# OpenBook.net
KiCad netlist of a schematic drawn in EAGLE
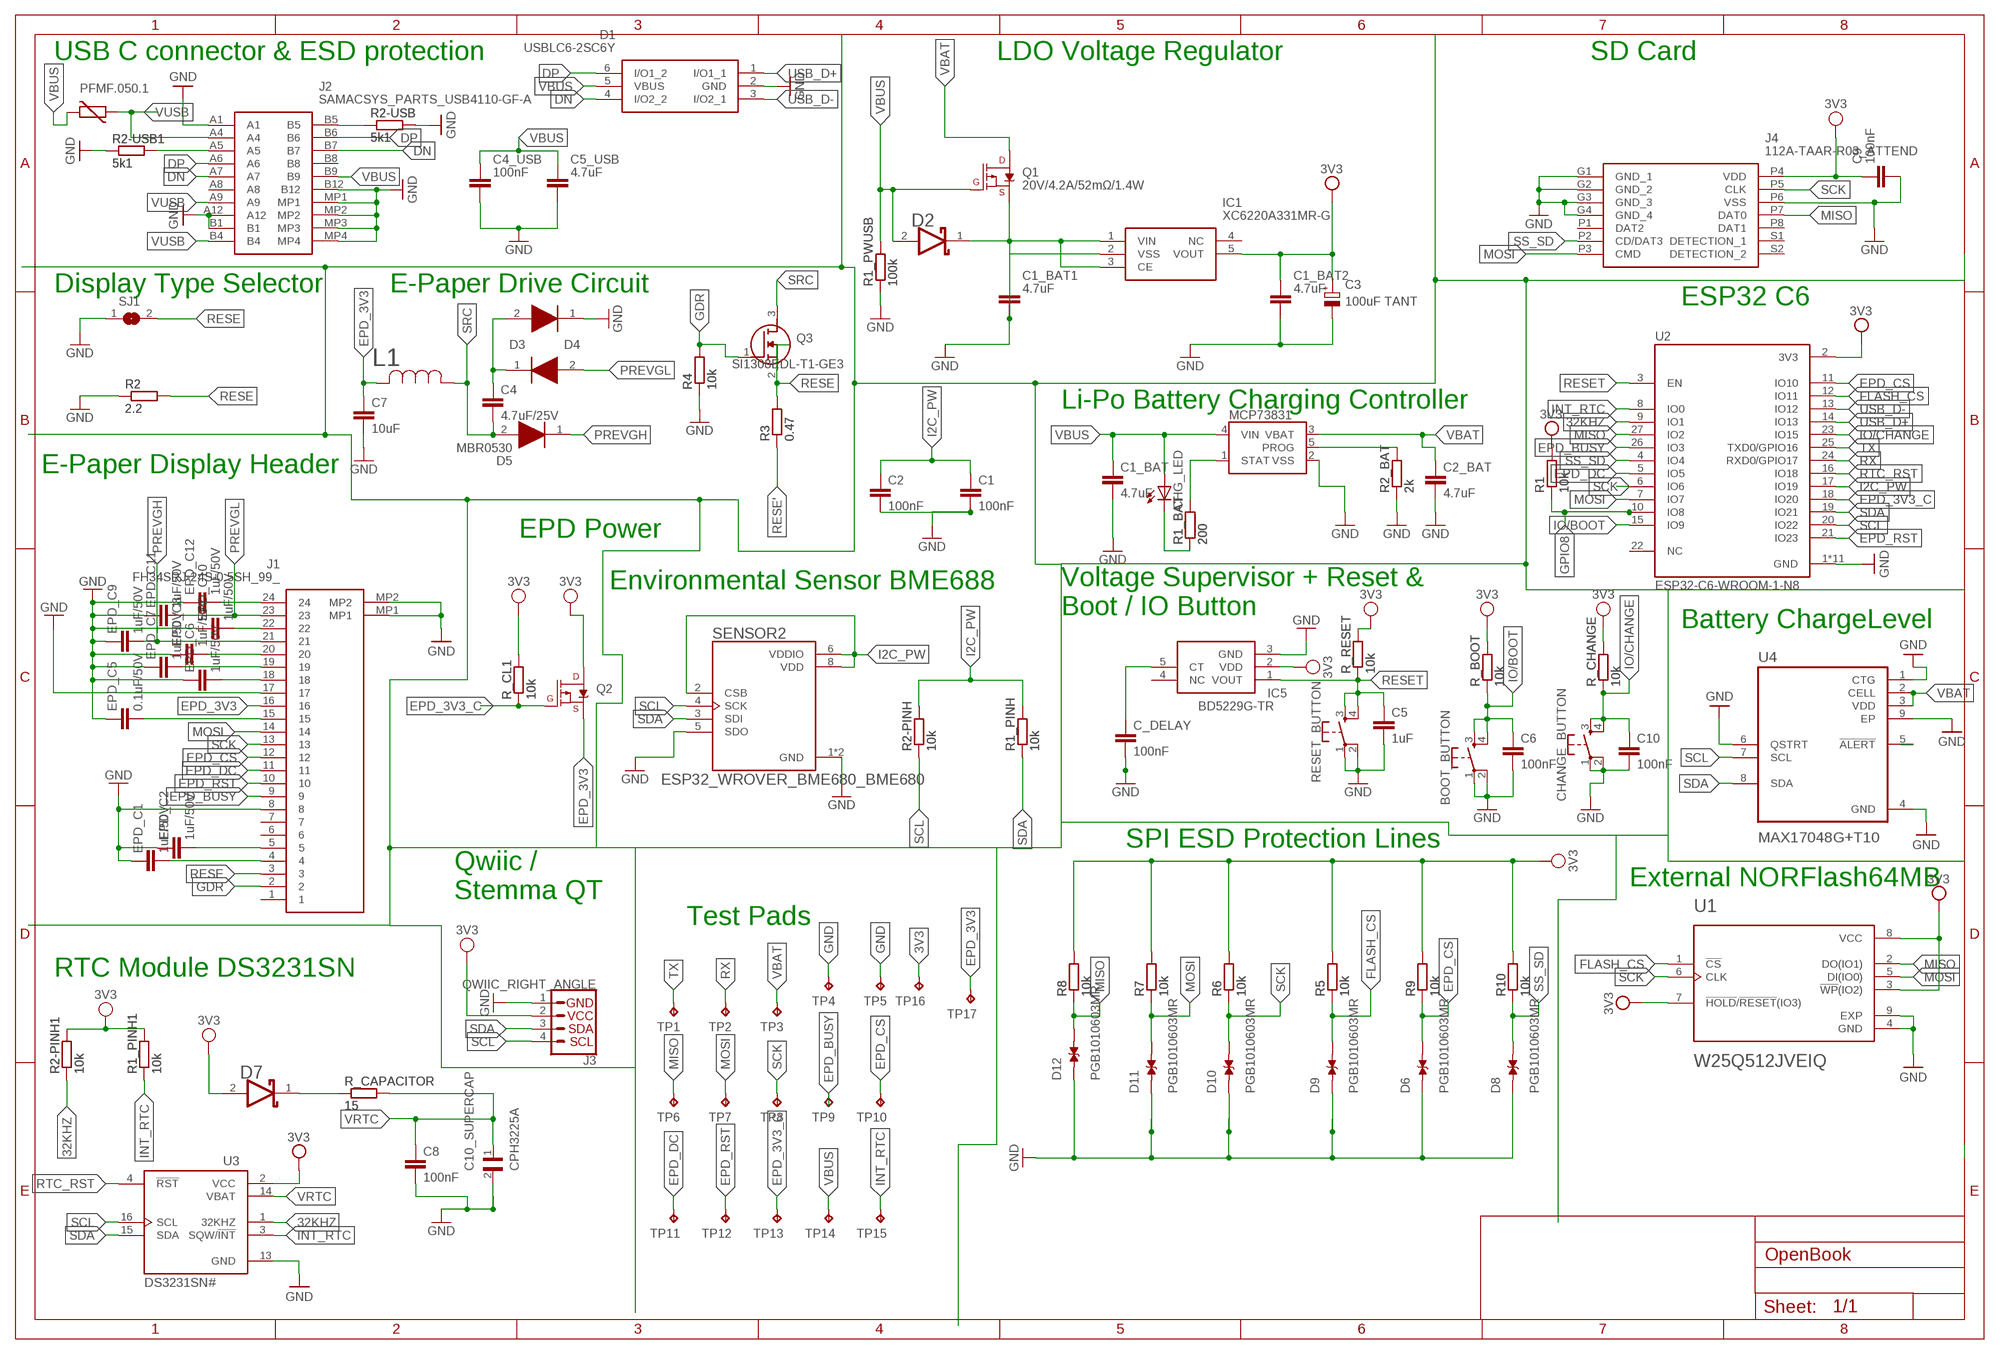
[diagram p0: schematic, sheet 1]

(export (version "E")
  (design (tool "Eeschema 10.0.6"))
  (components
    (comp (ref "BOOT_BUTTON")
      (value "BUTTON_CUSYOMV1")
      (footprint "eagle-import:MYBUTTON")
      (libsource (lib "eagle-import") (part "BUTTON_CUSYOMV1"))
    )
    (comp (ref "C1")
      (value "100nF")
      (footprint "eagle-import:ESP32_WROVER_EAGLE-LTSPICE_C0402")
      (libsource (lib "eagle-import") (part "ESP32_WROVER_EAGLE-LTSPICE_CC0402"))
    )
    (comp (ref "C1_BAT")
      (value "4.7uF")
      (footprint "eagle-import:ESP32_WROVER_EAGLE-LTSPICE_C0402")
      (libsource (lib "eagle-import") (part "ESP32_WROVER_EAGLE-LTSPICE_CC0402"))
    )
    (comp (ref "C1_BAT1")
      (value "4.7uF")
      (footprint "eagle-import:CAPC1005X60")
      (libsource (lib "eagle-import") (part "CCHIP-0402(1005-METRIC)_"))
    )
    (comp (ref "C1_BAT2")
      (value "4.7uF")
      (footprint "eagle-import:CAPM3216X180")
      (libsource (lib "eagle-import") (part "CTANTALUM-1206(3216-METRIC)_"))
    )
    (comp (ref "C2")
      (value "100nF")
      (footprint "eagle-import:ESP32_WROVER_EAGLE-LTSPICE_C0402")
      (libsource (lib "eagle-import") (part "ESP32_WROVER_EAGLE-LTSPICE_CC0402"))
    )
    (comp (ref "C2_BAT")
      (value "4.7uF")
      (footprint "eagle-import:ESP32_WROVER_EAGLE-LTSPICE_C0402")
      (libsource (lib "eagle-import") (part "ESP32_WROVER_EAGLE-LTSPICE_CC0402"))
    )
    (comp (ref "C3")
      (value "100uF TANT")
      (footprint "eagle-import:CAPMP3216X180N")
      (libsource (lib "eagle-import") (part "C-POLTANTALUM-1206(3216-METRIC)_"))
    )
    (comp (ref "C4")
      (value "4.7uF/25V")
      (footprint "eagle-import:EAGLE-LTSPICE_C0402")
      (libsource (lib "eagle-import") (part "EAGLE-LTSPICE_CC0402"))
    )
    (comp (ref "C4_USB")
      (value "100nF")
      (footprint "eagle-import:CAPC1005X60")
      (libsource (lib "eagle-import") (part "CCHIP-0402(1005-METRIC)_"))
    )
    (comp (ref "C5")
      (value "1uF")
      (footprint "eagle-import:ESP32_WROVER_EAGLE-LTSPICE_C0402")
      (libsource (lib "eagle-import") (part "ESP32_WROVER_EAGLE-LTSPICE_CC0402"))
    )
    (comp (ref "C5_USB")
      (value "4.7uF")
      (footprint "eagle-import:CAPC1005X60")
      (libsource (lib "eagle-import") (part "CCHIP-0402(1005-METRIC)_"))
    )
    (comp (ref "C6")
      (value "100nF")
      (footprint "eagle-import:ESP32_WROVER_EAGLE-LTSPICE_C0402")
      (libsource (lib "eagle-import") (part "ESP32_WROVER_EAGLE-LTSPICE_CC0402"))
    )
    (comp (ref "C7")
      (value "10uF")
      (footprint "eagle-import:EAGLE-LTSPICE_C0402")
      (libsource (lib "eagle-import") (part "EAGLE-LTSPICE_CC0402"))
    )
    (comp (ref "C8")
      (value "100nF")
      (footprint "eagle-import:EAGLE-LTSPICE_C0402")
      (libsource (lib "eagle-import") (part "EAGLE-LTSPICE_CC0402"))
    )
    (comp (ref "C9")
      (value "100nF")
      (footprint "eagle-import:CAPC1005X60")
      (libsource (lib "eagle-import") (part "CCHIP-0402(1005-METRIC)_"))
    )
    (comp (ref "C10")
      (value "100nF")
      (footprint "eagle-import:ESP32_WROVER_EAGLE-LTSPICE_C0402")
      (libsource (lib "eagle-import") (part "ESP32_WROVER_EAGLE-LTSPICE_CC0402"))
    )
    (comp (ref "C10_SUPERCAP")
      (value "CPH3225A")
      (footprint "eagle-import:CAPCP3225X100N")
      (fields (field (name "MF") "Seiko Instruments"))
      (libsource (lib "eagle-import") (part "CPH3225A"))
    )
    (comp (ref "CHANGE_BUTTON")
      (value "BUTTON_CUSYOMV1")
      (footprint "eagle-import:MYBUTTON")
      (libsource (lib "eagle-import") (part "BUTTON_CUSYOMV1"))
    )
    (comp (ref "CHG_LED")
      (value "ADAFRUIT_LEDCHIP-LED0603")
      (footprint "eagle-import:ADAFRUIT_CHIP-LED0603")
      (libsource (lib "eagle-import") (part "ADAFRUIT_LEDCHIP-LED0603"))
    )
    (comp (ref "C_DELAY")
      (value "100nF")
      (footprint "eagle-import:ESP32_WROVER_EAGLE-LTSPICE_C0402")
      (libsource (lib "eagle-import") (part "ESP32_WROVER_EAGLE-LTSPICE_CC0402"))
    )
    (comp (ref "D1")
      (value "USBLC6-2SC6Y")
      (footprint "eagle-import:SOT95P280X145-6N")
      (fields (field (name "MF") "STMicroelectronics"))
      (libsource (lib "eagle-import") (part "USBLC6-2SC6Y"))
    )
    (comp (ref "D2")
      (value "ESP32_WROVER_AVX---SD0805S020S1R0_AVX_SD0805S020S1R0_0_0AVX_SD0805S020S1R0_0_0")
      (footprint "eagle-import:ESP32_WROVER_AVX---SD0805S020S1R0_AVX_SD0805S020S1R0_0")
      (fields
        (field (name "DIGIKEY_PART_NUMBER") "478-7800-1-ND")
        (field (name "MF") "AVX")
        (field (name "MOUSER_PART_NUMBER") "581-SD0805S020S1R0")
      )
      (libsource (lib "eagle-import") (part "ESP32_WROVER_AVX---SD0805S020S1R0_AVX_SD0805S020S1R0_0_0AVX_SD0805S020S1R0_0_0"))
    )
    (comp (ref "D3")
      (value "MBR0530")
      (footprint "eagle-import:SOD3716X135N")
      (fields (field (name "MF") "ON Semiconductor"))
      (libsource (lib "eagle-import") (part "MBR0530"))
    )
    (comp (ref "D4")
      (value "MBR0530")
      (footprint "eagle-import:SOD3716X135N")
      (fields (field (name "MF") "ON Semiconductor"))
      (libsource (lib "eagle-import") (part "MBR0530"))
    )
    (comp (ref "D5")
      (value "MBR0530")
      (footprint "eagle-import:SOD3716X135N")
      (fields (field (name "MF") "ON Semiconductor"))
      (libsource (lib "eagle-import") (part "MBR0530"))
    )
    (comp (ref "D6")
      (value "PGB1010603MR")
      (footprint "eagle-import:DIOC1608X36N")
      (fields (field (name "MF") "Littelfuse Inc."))
      (libsource (lib "eagle-import") (part "PGB1010603MR"))
    )
    (comp (ref "D7")
      (value "ESP32_WROVER_AVX---SD0805S020S1R0_AVX_SD0805S020S1R0_0_0AVX_SD0805S020S1R0_0_0")
      (footprint "eagle-import:ESP32_WROVER_AVX---SD0805S020S1R0_AVX_SD0805S020S1R0_0")
      (fields
        (field (name "DIGIKEY_PART_NUMBER") "478-7800-1-ND")
        (field (name "MF") "AVX")
        (field (name "MOUSER_PART_NUMBER") "581-SD0805S020S1R0")
      )
      (libsource (lib "eagle-import") (part "ESP32_WROVER_AVX---SD0805S020S1R0_AVX_SD0805S020S1R0_0_0AVX_SD0805S020S1R0_0_0"))
    )
    (comp (ref "D8")
      (value "PGB1010603MR")
      (footprint "eagle-import:DIOC1608X36N")
      (fields (field (name "MF") "Littelfuse Inc."))
      (libsource (lib "eagle-import") (part "PGB1010603MR"))
    )
    (comp (ref "D9")
      (value "PGB1010603MR")
      (footprint "eagle-import:DIOC1608X36N")
      (fields (field (name "MF") "Littelfuse Inc."))
      (libsource (lib "eagle-import") (part "PGB1010603MR"))
    )
    (comp (ref "D10")
      (value "PGB1010603MR")
      (footprint "eagle-import:DIOC1608X36N")
      (fields (field (name "MF") "Littelfuse Inc."))
      (libsource (lib "eagle-import") (part "PGB1010603MR"))
    )
    (comp (ref "D11")
      (value "PGB1010603MR")
      (footprint "eagle-import:DIOC1608X36N")
      (fields (field (name "MF") "Littelfuse Inc."))
      (libsource (lib "eagle-import") (part "PGB1010603MR"))
    )
    (comp (ref "D12")
      (value "PGB1010603MR")
      (footprint "eagle-import:DIOC1608X36N")
      (fields (field (name "MF") "Littelfuse Inc."))
      (libsource (lib "eagle-import") (part "PGB1010603MR"))
    )
    (comp (ref "EPD_C1")
      (value "1uF/50V")
      (footprint "eagle-import:ESP32_WROVER_EAGLE-LTSPICE_C0402")
      (libsource (lib "eagle-import") (part "ESP32_WROVER_EAGLE-LTSPICE_CC0402"))
    )
    (comp (ref "EPD_C2")
      (value "1uF/50V")
      (footprint "eagle-import:ESP32_WROVER_EAGLE-LTSPICE_C0402")
      (libsource (lib "eagle-import") (part "ESP32_WROVER_EAGLE-LTSPICE_CC0402"))
    )
    (comp (ref "EPD_C5")
      (value "0.1uF/50V")
      (footprint "eagle-import:ESP32_WROVER_EAGLE-LTSPICE_C0402")
      (libsource (lib "eagle-import") (part "ESP32_WROVER_EAGLE-LTSPICE_CC0402"))
    )
    (comp (ref "EPD_C6")
      (value "1uF/50V")
      (footprint "eagle-import:ESP32_WROVER_EAGLE-LTSPICE_C0402")
      (libsource (lib "eagle-import") (part "ESP32_WROVER_EAGLE-LTSPICE_CC0402"))
    )
    (comp (ref "EPD_C7")
      (value "1uF/50V")
      (footprint "eagle-import:ESP32_WROVER_EAGLE-LTSPICE_C0402")
      (libsource (lib "eagle-import") (part "ESP32_WROVER_EAGLE-LTSPICE_CC0402"))
    )
    (comp (ref "EPD_C8")
      (value "1uF/50V")
      (footprint "eagle-import:ESP32_WROVER_EAGLE-LTSPICE_C0402")
      (libsource (lib "eagle-import") (part "ESP32_WROVER_EAGLE-LTSPICE_CC0402"))
    )
    (comp (ref "EPD_C9")
      (value "1uF/50V")
      (footprint "eagle-import:ESP32_WROVER_EAGLE-LTSPICE_C0402")
      (libsource (lib "eagle-import") (part "ESP32_WROVER_EAGLE-LTSPICE_CC0402"))
    )
    (comp (ref "EPD_C10")
      (value "1uF/50V")
      (footprint "eagle-import:ESP32_WROVER_EAGLE-LTSPICE_C0402")
      (libsource (lib "eagle-import") (part "ESP32_WROVER_EAGLE-LTSPICE_CC0402"))
    )
    (comp (ref "EPD_C11")
      (value "1uF/50V")
      (footprint "eagle-import:ESP32_WROVER_EAGLE-LTSPICE_C0402")
      (libsource (lib "eagle-import") (part "ESP32_WROVER_EAGLE-LTSPICE_CC0402"))
    )
    (comp (ref "EPD_C12")
      (value "1uF/50V")
      (footprint "eagle-import:ESP32_WROVER_EAGLE-LTSPICE_C0402")
      (libsource (lib "eagle-import") (part "ESP32_WROVER_EAGLE-LTSPICE_CC0402"))
    )
    (comp (ref "IC1")
      (value "XC6220A331MR-G")
      (footprint "eagle-import:SOT95P280X120-5N")
      (fields (field (name "MOUSER_PART_NUMBER") "865-XC6220A331MR-G"))
      (libsource (lib "eagle-import") (part "XC6220A331MR-G"))
    )
    (comp (ref "IC5")
      (value "BD5229G-TR")
      (footprint "eagle-import:SOT95P280X125-5N")
      (fields (field (name "MOUSER_PART_NUMBER") "755-BD5229G-TR"))
      (libsource (lib "eagle-import") (part "BD5229G-TR"))
    )
    (comp (ref "J1")
      (value "FH34SRJ-24S-0.5SH_99_")
      (footprint "eagle-import:FH34SRJ24S05SH99")
      (fields
        (field (name "MANUFACTURER_PART_NUMBER") "FH34SRJ-24S-0.5SH(99)")
        (field (name "MOUSER_PART_NUMBER") "798-FH34SRJ24S05SH99")
      )
      (libsource (lib "eagle-import") (part "FH34SRJ-24S-0.5SH_99_"))
    )
    (comp (ref "J2")
      (value "SAMACSYS_PARTS_USB4110-GF-A")
      (footprint "eagle-import:SAMACSYS_PARTS_USB4110GFA")
      (fields
        (field (name "MANUFACTURER_PART_NUMBER") "USB4110-GF-A")
        (field (name "MOUSER_PART_NUMBER") "640-USB4110-GF-A")
      )
      (libsource (lib "eagle-import") (part "SAMACSYS_PARTS_USB4110-GF-A"))
    )
    (comp (ref "J3")
      (value "QWIIC_RIGHT_ANGLE")
      (footprint "eagle-import:JST04_1MM_RA")
      (libsource (lib "eagle-import") (part "QWIIC_CONNECTORJS-1MM"))
    )
    (comp (ref "J4")
      (value "112A-TAAR-R03_ATTEND")
      (footprint "eagle-import:112ATAARR03ATTEND")
      (fields (field (name "MANUFACTURER_PART_NUMBER") "112A-TAAR-R03 ATTEND"))
      (libsource (lib "eagle-import") (part "112A-TAAR-R03_ATTEND"))
    )
    (comp (ref "L1")
      (value "68uH")
      (footprint "eagle-import:IND_4828-WE-TPC_WRE")
      (fields
        (field (name "MANUFACTURER_PART_NUMBER") "744043680")
        (field (name "COPYRIGHT") "Copyright (C) 2024 Ultra Librarian. All rights reserved.")
      )
      (libsource (lib "eagle-import") (part "744043680IND_4828-WE-TPC_WRE"))
    )
    (comp (ref "MCP73831")
      (value "ESP32_WROVER_SPARKFUN-IC-POWER_MCP73831")
      (footprint "eagle-import:ESP32_WROVER_SPARKFUN-IC-POWER_SOT23-5")
      (libsource (lib "eagle-import") (part "ESP32_WROVER_SPARKFUN-IC-POWER_MCP73831"))
    )
    (comp (ref "PFMF.050.1")
      (value "ESP32C6_VARISTORCN1812")
      (footprint "eagle-import:ESP32C6_VARISTOR_CT_CN1812")
      (libsource (lib "eagle-import") (part "ESP32C6_VARISTORCN1812"))
    )
    (comp (ref "Q1")
      (value "20V/4.2A/52mΩ/1.4W")
      (footprint "eagle-import:ESP32_WROVER_SPARKFUN-DISCRETESEMI_SOT23-3")
      (libsource (lib "eagle-import") (part "ESP32_WROVER_SPARKFUN-DISCRETESEMI_MOSFET_PCH-DMG2305UX-7"))
    )
    (comp (ref "Q2")
      (value "20V/4.2A/52mΩ/1.4W")
      (footprint "eagle-import:ESP32_WROVER_SPARKFUN-DISCRETESEMI_SOT23-3")
      (libsource (lib "eagle-import") (part "ESP32_WROVER_SPARKFUN-DISCRETESEMI_MOSFET_PCH-DMG2305UX-7"))
    )
    (comp (ref "Q3")
      (value "SI1308EDL-T1-GE3")
      (footprint "eagle-import:SOT65P210X110-3N")
      (fields
        (field (name "MANUFACTURER_PART_NUMBER") "Si1308EDL-T1-GE3")
        (field (name "MOUSER_PART_NUMBER") "78-SI1308EDL-T1-GE3")
      )
      (libsource (lib "eagle-import") (part "SI1308EDL-T1-GE3"))
    )
    (comp (ref "R1")
      (value "10k")
      (footprint "eagle-import:ESP32_WROVER_EAGLE-LTSPICE_R0402")
      (libsource (lib "eagle-import") (part "ESP32_WROVER_EAGLE-LTSPICE_RR0402"))
    )
    (comp (ref "R1_BAT")
      (value "200")
      (footprint "eagle-import:ESP32_WROVER_EAGLE-LTSPICE_R0402")
      (libsource (lib "eagle-import") (part "ESP32_WROVER_EAGLE-LTSPICE_RR0402"))
    )
    (comp (ref "R1_PINH")
      (value "10k")
      (footprint "eagle-import:ESP32_WROVER_EAGLE-LTSPICE_R0402")
      (libsource (lib "eagle-import") (part "ESP32_WROVER_EAGLE-LTSPICE_RR0402"))
    )
    (comp (ref "R1_PINH1")
      (value "10k")
      (footprint "eagle-import:ESP32_WROVER_EAGLE-LTSPICE_R0402")
      (libsource (lib "eagle-import") (part "ESP32_WROVER_EAGLE-LTSPICE_RR0402"))
    )
    (comp (ref "R1_PWUSB")
      (value "100k")
      (footprint "eagle-import:ESP32_WROVER_EAGLE-LTSPICE_R0402")
      (libsource (lib "eagle-import") (part "ESP32_WROVER_EAGLE-LTSPICE_RR0402"))
    )
    (comp (ref "R2")
      (value "2.2")
      (footprint "eagle-import:ESP32_WROVER_EAGLE-LTSPICE_R0402")
      (libsource (lib "eagle-import") (part "ESP32_WROVER_EAGLE-LTSPICE_RR0402"))
    )
    (comp (ref "R2-PINH")
      (value "10k")
      (footprint "eagle-import:ESP32_WROVER_EAGLE-LTSPICE_R0402")
      (libsource (lib "eagle-import") (part "ESP32_WROVER_EAGLE-LTSPICE_RR0402"))
    )
    (comp (ref "R2-PINH1")
      (value "10k")
      (footprint "eagle-import:ESP32_WROVER_EAGLE-LTSPICE_R0402")
      (libsource (lib "eagle-import") (part "ESP32_WROVER_EAGLE-LTSPICE_RR0402"))
    )
    (comp (ref "R2-USB")
      (value "5k1")
      (footprint "eagle-import:ESP32_WROVER_EAGLE-LTSPICE_R0402")
      (libsource (lib "eagle-import") (part "ESP32_WROVER_EAGLE-LTSPICE_RR0402"))
    )
    (comp (ref "R2-USB1")
      (value "5k1")
      (footprint "eagle-import:ESP32_WROVER_EAGLE-LTSPICE_R0402")
      (libsource (lib "eagle-import") (part "ESP32_WROVER_EAGLE-LTSPICE_RR0402"))
    )
    (comp (ref "R2_BAT")
      (value "2k")
      (footprint "eagle-import:ESP32_WROVER_EAGLE-LTSPICE_R0402")
      (libsource (lib "eagle-import") (part "ESP32_WROVER_EAGLE-LTSPICE_RR0402"))
    )
    (comp (ref "R3")
      (value "0.47")
      (footprint "eagle-import:ESP32_WROVER_EAGLE-LTSPICE_R0402")
      (libsource (lib "eagle-import") (part "ESP32_WROVER_EAGLE-LTSPICE_RR0402"))
    )
    (comp (ref "R4")
      (value "10k")
      (footprint "eagle-import:ESP32_WROVER_EAGLE-LTSPICE_R0402")
      (libsource (lib "eagle-import") (part "ESP32_WROVER_EAGLE-LTSPICE_RR0402"))
    )
    (comp (ref "R5")
      (value "10k")
      (footprint "eagle-import:ESP32_WROVER_EAGLE-LTSPICE_R0402")
      (libsource (lib "eagle-import") (part "ESP32_WROVER_EAGLE-LTSPICE_RR0402"))
    )
    (comp (ref "R6")
      (value "10k")
      (footprint "eagle-import:ESP32_WROVER_EAGLE-LTSPICE_R0402")
      (libsource (lib "eagle-import") (part "ESP32_WROVER_EAGLE-LTSPICE_RR0402"))
    )
    (comp (ref "R7")
      (value "10k")
      (footprint "eagle-import:ESP32_WROVER_EAGLE-LTSPICE_R0402")
      (libsource (lib "eagle-import") (part "ESP32_WROVER_EAGLE-LTSPICE_RR0402"))
    )
    (comp (ref "R8")
      (value "10k")
      (footprint "eagle-import:ESP32_WROVER_EAGLE-LTSPICE_R0402")
      (libsource (lib "eagle-import") (part "ESP32_WROVER_EAGLE-LTSPICE_RR0402"))
    )
    (comp (ref "R9")
      (value "10k")
      (footprint "eagle-import:ESP32_WROVER_EAGLE-LTSPICE_R0402")
      (libsource (lib "eagle-import") (part "ESP32_WROVER_EAGLE-LTSPICE_RR0402"))
    )
    (comp (ref "R10")
      (value "10k")
      (footprint "eagle-import:ESP32_WROVER_EAGLE-LTSPICE_R0402")
      (libsource (lib "eagle-import") (part "ESP32_WROVER_EAGLE-LTSPICE_RR0402"))
    )
    (comp (ref "RESET_BUTTON")
      (value "BUTTON_CUSYOMV1")
      (footprint "eagle-import:MYBUTTON")
      (libsource (lib "eagle-import") (part "BUTTON_CUSYOMV1"))
    )
    (comp (ref "R_BOOT")
      (value "10k")
      (footprint "eagle-import:ESP32_WROVER_EAGLE-LTSPICE_R0402")
      (libsource (lib "eagle-import") (part "ESP32_WROVER_EAGLE-LTSPICE_RR0402"))
    )
    (comp (ref "R_CAPACITOR")
      (value "15")
      (footprint "eagle-import:ESP32_WROVER_EAGLE-LTSPICE_R0402")
      (libsource (lib "eagle-import") (part "ESP32_WROVER_EAGLE-LTSPICE_RR0402"))
    )
    (comp (ref "R_CHANGE")
      (value "10k")
      (footprint "eagle-import:ESP32_WROVER_EAGLE-LTSPICE_R0402")
      (libsource (lib "eagle-import") (part "ESP32_WROVER_EAGLE-LTSPICE_RR0402"))
    )
    (comp (ref "R_CL1")
      (value "10k")
      (footprint "eagle-import:ESP32_WROVER_EAGLE-LTSPICE_R0402")
      (libsource (lib "eagle-import") (part "ESP32_WROVER_EAGLE-LTSPICE_RR0402"))
    )
    (comp (ref "R_RESET")
      (value "10k")
      (footprint "eagle-import:ESP32_WROVER_EAGLE-LTSPICE_R0402")
      (libsource (lib "eagle-import") (part "ESP32_WROVER_EAGLE-LTSPICE_RR0402"))
    )
    (comp (ref "SENSOR2")
      (value "ESP32_WROVER_BME680_BME680")
      (footprint "eagle-import:ESP32_WROVER_BME680_PSON80P300X300X100-8N")
      (fields (field (name "MF") "Bosch Sensortec") (field (name "MP") "BME680"))
      (libsource (lib "eagle-import") (part "ESP32_WROVER_BME680_BME680"))
    )
    (comp (ref "SJ1") (value "SJ") (footprint "eagle-import:SJ") (libsource (lib "eagle-import") (part "SJ")))
    (comp (ref "TP1")
      (value "TPB1,27")
      (footprint "eagle-import:B1,27")
      (libsource (lib "eagle-import") (part "TPB1,27"))
    )
    (comp (ref "TP2")
      (value "TPB1,27")
      (footprint "eagle-import:B1,27")
      (libsource (lib "eagle-import") (part "TPB1,27"))
    )
    (comp (ref "TP3")
      (value "TPB1,27")
      (footprint "eagle-import:B1,27")
      (libsource (lib "eagle-import") (part "TPB1,27"))
    )
    (comp (ref "TP4")
      (value "TPB1,27")
      (footprint "eagle-import:B1,27")
      (libsource (lib "eagle-import") (part "TPB1,27"))
    )
    (comp (ref "TP5")
      (value "TPB1,27")
      (footprint "eagle-import:B1,27")
      (libsource (lib "eagle-import") (part "TPB1,27"))
    )
    (comp (ref "TP6")
      (value "TPB1,27")
      (footprint "eagle-import:B1,27")
      (libsource (lib "eagle-import") (part "TPB1,27"))
    )
    (comp (ref "TP7")
      (value "TPB1,27")
      (footprint "eagle-import:B1,27")
      (libsource (lib "eagle-import") (part "TPB1,27"))
    )
    (comp (ref "TP8")
      (value "TPB1,27")
      (footprint "eagle-import:B1,27")
      (libsource (lib "eagle-import") (part "TPB1,27"))
    )
    (comp (ref "TP9")
      (value "TPB1,27")
      (footprint "eagle-import:B1,27")
      (libsource (lib "eagle-import") (part "TPB1,27"))
    )
    (comp (ref "TP10")
      (value "TPB1,27")
      (footprint "eagle-import:B1,27")
      (libsource (lib "eagle-import") (part "TPB1,27"))
    )
    (comp (ref "TP11")
      (value "TPB1,27")
      (footprint "eagle-import:B1,27")
      (libsource (lib "eagle-import") (part "TPB1,27"))
    )
    (comp (ref "TP12")
      (value "TPB1,27")
      (footprint "eagle-import:B1,27")
      (libsource (lib "eagle-import") (part "TPB1,27"))
    )
    (comp (ref "TP13")
      (value "TPB1,27")
      (footprint "eagle-import:B1,27")
      (libsource (lib "eagle-import") (part "TPB1,27"))
    )
    (comp (ref "TP14")
      (value "TPB1,27")
      (footprint "eagle-import:B1,27")
      (libsource (lib "eagle-import") (part "TPB1,27"))
    )
    (comp (ref "TP15")
      (value "TPB1,27")
      (footprint "eagle-import:B1,27")
      (libsource (lib "eagle-import") (part "TPB1,27"))
    )
    (comp (ref "TP16")
      (value "TPB1,27")
      (footprint "eagle-import:B1,27")
      (libsource (lib "eagle-import") (part "TPB1,27"))
    )
    (comp (ref "TP17")
      (value "TPB1,27")
      (footprint "eagle-import:B1,27")
      (libsource (lib "eagle-import") (part "TPB1,27"))
    )
    (comp (ref "U1")
      (value "W25Q512JVEIQ")
      (footprint "eagle-import:SON127P600X800X80-9N")
      (fields (field (name "MF") "Winbond Electronics"))
      (libsource (lib "eagle-import") (part "W25Q512JVEIQ"))
    )
    (comp (ref "U2")
      (value "ESP32-C6-WROOM-1-N8")
      (footprint "eagle-import:XCVR_ESP32-C6-WROOM-1-N8")
      (fields (field (name "MF") "Espressif Systems"))
      (libsource (lib "eagle-import") (part "ESP32-C6-WROOM-1-N8"))
    )
    (comp (ref "U3")
      (value "DS3231SN#")
      (footprint "eagle-import:SOIC127P1032X265-16N")
      (fields (field (name "MF") "Analog Devices"))
      (libsource (lib "eagle-import") (part "DS3231SN#"))
    )
    (comp (ref "U4")
      (value "MAX17048G+T10")
      (footprint "eagle-import:SON50P200X200X80-9N")
      (fields (field (name "MF") "Analog Devices"))
      (libsource (lib "eagle-import") (part "MAX17048G+T10"))
    )
  )
  (nets
    (net (code "1") (name "3V3") (class "Default")
      (node (ref "C1_BAT2") (pin "1") (pinfunction "1_1") (pintype "passive"))
      (node (ref "C3") (pin "1") (pinfunction "+_1") (pintype "passive"))
      (node (ref "C9") (pin "1") (pinfunction "1_1") (pintype "passive"))
      (node (ref "D7") (pin "2") (pinfunction "ANODE_2") (pintype "bidirectional"))
      (node (ref "IC1") (pin "5") (pinfunction "VOUT_5") (pintype "bidirectional"))
      (node (ref "IC5") (pin "2") (pinfunction "VDD_2") (pintype "bidirectional"))
      (node (ref "J3") (pin "2") (pinfunction "2_2") (pintype "power_in"))
      (node (ref "J4") (pin "P4") (pinfunction "VDD_P4") (pintype "bidirectional"))
      (node (ref "Q2") (pin "3") (pinfunction "D_3") (pintype "bidirectional"))
      (node (ref "R1") (pin "2") (pinfunction "2_2") (pintype "passive"))
      (node (ref "R10") (pin "2") (pinfunction "2_2") (pintype "passive"))
      (node (ref "R1_PINH1") (pin "2") (pinfunction "2_2") (pintype "passive"))
      (node (ref "R2-PINH1") (pin "2") (pinfunction "2_2") (pintype "passive"))
      (node (ref "R5") (pin "2") (pinfunction "2_2") (pintype "passive"))
      (node (ref "R6") (pin "2") (pinfunction "2_2") (pintype "passive"))
      (node (ref "R7") (pin "2") (pinfunction "2_2") (pintype "passive"))
      (node (ref "R8") (pin "2") (pinfunction "2_2") (pintype "passive"))
      (node (ref "R9") (pin "2") (pinfunction "2_2") (pintype "passive"))
      (node (ref "R_BOOT") (pin "2") (pinfunction "2_2") (pintype "passive"))
      (node (ref "R_CHANGE") (pin "2") (pinfunction "2_2") (pintype "passive"))
      (node (ref "R_CL1") (pin "2") (pinfunction "2_2") (pintype "passive"))
      (node (ref "R_RESET") (pin "2") (pinfunction "2_2") (pintype "passive"))
      (node (ref "TP16") (pin "TP") (pinfunction "TP_TP") (pintype "input"))
      (node (ref "U1") (pin "3") (pinfunction "~{WP}(IO2)_3") (pintype "bidirectional"))
      (node (ref "U1") (pin "7") (pinfunction "~{HOLD}/~{RESET}(IO3)_7") (pintype "bidirectional"))
      (node (ref "U1") (pin "8") (pinfunction "VCC_8") (pintype "power_in"))
      (node (ref "U2") (pin "2") (pinfunction "3V3_2") (pintype "power_in"))
      (node (ref "U3") (pin "2") (pinfunction "VCC_2") (pintype "power_in"))
    )
    (net (code "2") (name "32KHZ") (class "Default")
      (node (ref "R2-PINH1") (pin "1") (pinfunction "1_1") (pintype "passive"))
      (node (ref "U2") (pin "9") (pinfunction "IO1_9") (pintype "bidirectional"))
      (node (ref "U3") (pin "1") (pinfunction "32KHZ_1") (pintype "output"))
    )
    (net (code "3") (name "DN") (class "Default")
      (node (ref "D1") (pin "4") (pinfunction "I/O2_2_4") (pintype "bidirectional"))
      (node (ref "J2") (pin "A7") (pinfunction "A7_A7") (pintype "bidirectional"))
      (node (ref "J2") (pin "B7") (pinfunction "B7_B7") (pintype "bidirectional"))
    )
    (net (code "4") (name "DP") (class "Default")
      (node (ref "D1") (pin "6") (pinfunction "I/O1_2_6") (pintype "bidirectional"))
      (node (ref "J2") (pin "A6") (pinfunction "A6_A6") (pintype "bidirectional"))
      (node (ref "J2") (pin "B6") (pinfunction "B6_B6") (pintype "bidirectional"))
    )
    (net (code "5") (name "EPD_3V3") (class "Default")
      (node (ref "C7") (pin "1") (pinfunction "1_1") (pintype "passive"))
      (node (ref "J1") (pin "16") (pinfunction "16_16") (pintype "bidirectional"))
      (node (ref "L1") (pin "2") (pinfunction "2_2") (pintype "passive"))
      (node (ref "Q2") (pin "2") (pinfunction "S_2") (pintype "bidirectional"))
      (node (ref "TP17") (pin "TP") (pinfunction "TP_TP") (pintype "input"))
    )
    (net (code "6") (name "EPD_3V3_C") (class "Default")
      (node (ref "Q2") (pin "1") (pinfunction "G_1") (pintype "bidirectional"))
      (node (ref "R_CL1") (pin "1") (pinfunction "1_1") (pintype "passive"))
      (node (ref "TP13") (pin "TP") (pinfunction "TP_TP") (pintype "input"))
      (node (ref "U2") (pin "18") (pinfunction "IO20_18") (pintype "bidirectional"))
    )
    (net (code "7") (name "EPD_BUSY") (class "Default")
      (node (ref "J1") (pin "9") (pinfunction "9_9") (pintype "bidirectional"))
      (node (ref "TP9") (pin "TP") (pinfunction "TP_TP") (pintype "input"))
      (node (ref "U2") (pin "26") (pinfunction "IO3_26") (pintype "bidirectional"))
    )
    (net (code "8") (name "EPD_CS") (class "Default")
      (node (ref "D6") (pin "2") (pinfunction "2_2") (pintype "passive"))
      (node (ref "J1") (pin "12") (pinfunction "12_12") (pintype "bidirectional"))
      (node (ref "R9") (pin "1") (pinfunction "1_1") (pintype "passive"))
      (node (ref "TP10") (pin "TP") (pinfunction "TP_TP") (pintype "input"))
      (node (ref "U2") (pin "11") (pinfunction "IO10_11") (pintype "bidirectional"))
    )
    (net (code "9") (name "EPD_DC") (class "Default")
      (node (ref "J1") (pin "11") (pinfunction "11_11") (pintype "bidirectional"))
      (node (ref "TP11") (pin "TP") (pinfunction "TP_TP") (pintype "input"))
      (node (ref "U2") (pin "5") (pinfunction "IO5_5") (pintype "bidirectional"))
    )
    (net (code "10") (name "EPD_RST") (class "Default")
      (node (ref "J1") (pin "10") (pinfunction "10_10") (pintype "bidirectional"))
      (node (ref "TP12") (pin "TP") (pinfunction "TP_TP") (pintype "input"))
      (node (ref "U2") (pin "21") (pinfunction "IO23_21") (pintype "bidirectional"))
    )
    (net (code "11") (name "FLASH_CS") (class "Default")
      (node (ref "D9") (pin "2") (pinfunction "2_2") (pintype "passive"))
      (node (ref "R5") (pin "1") (pinfunction "1_1") (pintype "passive"))
      (node (ref "U1") (pin "1") (pinfunction "~{CS}_1") (pintype "input"))
      (node (ref "U2") (pin "12") (pinfunction "IO11_12") (pintype "bidirectional"))
    )
    (net (code "12") (name "GDR") (class "Default")
      (node (ref "J1") (pin "2") (pinfunction "2_2") (pintype "bidirectional"))
      (node (ref "Q3") (pin "1") (pinfunction "G_1") (pintype "bidirectional"))
      (node (ref "R4") (pin "2") (pinfunction "2_2") (pintype "passive"))
    )
    (net (code "13") (name "GND") (class "Default")
      (node (ref "BOOT_BUTTON") (pin "1") (pinfunction "1_1") (pintype "passive"))
      (node (ref "BOOT_BUTTON") (pin "2") (pinfunction "2_2") (pintype "passive"))
      (node (ref "C1") (pin "2") (pinfunction "2_2") (pintype "passive"))
      (node (ref "C10") (pin "2") (pinfunction "2_2") (pintype "passive"))
      (node (ref "C10_SUPERCAP") (pin "2") (pinfunction "2_2") (pintype "passive"))
      (node (ref "C1_BAT") (pin "2") (pinfunction "2_2") (pintype "passive"))
      (node (ref "C1_BAT1") (pin "2") (pinfunction "2_2") (pintype "passive"))
      (node (ref "C1_BAT2") (pin "2") (pinfunction "2_2") (pintype "passive"))
      (node (ref "C2") (pin "2") (pinfunction "2_2") (pintype "passive"))
      (node (ref "C2_BAT") (pin "2") (pinfunction "2_2") (pintype "passive"))
      (node (ref "C3") (pin "2") (pinfunction "-_2") (pintype "passive"))
      (node (ref "C4_USB") (pin "2") (pinfunction "2_2") (pintype "passive"))
      (node (ref "C5") (pin "2") (pinfunction "2_2") (pintype "passive"))
      (node (ref "C5_USB") (pin "2") (pinfunction "2_2") (pintype "passive"))
      (node (ref "C6") (pin "2") (pinfunction "2_2") (pintype "passive"))
      (node (ref "C7") (pin "2") (pinfunction "2_2") (pintype "passive"))
      (node (ref "C8") (pin "2") (pinfunction "2_2") (pintype "passive"))
      (node (ref "C9") (pin "2") (pinfunction "2_2") (pintype "passive"))
      (node (ref "CHANGE_BUTTON") (pin "1") (pinfunction "1_1") (pintype "passive"))
      (node (ref "CHANGE_BUTTON") (pin "2") (pinfunction "2_2") (pintype "passive"))
      (node (ref "C_DELAY") (pin "2") (pinfunction "2_2") (pintype "passive"))
      (node (ref "D1") (pin "2") (pinfunction "GND_2") (pintype "bidirectional"))
      (node (ref "D10") (pin "1") (pinfunction "1_1") (pintype "passive"))
      (node (ref "D11") (pin "1") (pinfunction "1_1") (pintype "passive"))
      (node (ref "D12") (pin "1") (pinfunction "1_1") (pintype "passive"))
      (node (ref "D3") (pin "1") (pinfunction "K_1") (pintype "bidirectional"))
      (node (ref "D6") (pin "1") (pinfunction "1_1") (pintype "passive"))
      (node (ref "D8") (pin "1") (pinfunction "1_1") (pintype "passive"))
      (node (ref "D9") (pin "1") (pinfunction "1_1") (pintype "passive"))
      (node (ref "EPD_C1") (pin "1") (pinfunction "1_1") (pintype "passive"))
      (node (ref "EPD_C10") (pin "1") (pinfunction "1_1") (pintype "passive"))
      (node (ref "EPD_C11") (pin "1") (pinfunction "1_1") (pintype "passive"))
      (node (ref "EPD_C12") (pin "1") (pinfunction "1_1") (pintype "passive"))
      (node (ref "EPD_C2") (pin "1") (pinfunction "1_1") (pintype "passive"))
      (node (ref "EPD_C5") (pin "1") (pinfunction "1_1") (pintype "passive"))
      (node (ref "EPD_C6") (pin "1") (pinfunction "1_1") (pintype "passive"))
      (node (ref "EPD_C7") (pin "1") (pinfunction "1_1") (pintype "passive"))
      (node (ref "EPD_C8") (pin "1") (pinfunction "1_1") (pintype "passive"))
      (node (ref "EPD_C9") (pin "1") (pinfunction "1_1") (pintype "passive"))
      (node (ref "IC1") (pin "2") (pinfunction "VSS_2") (pintype "bidirectional"))
      (node (ref "IC5") (pin "3") (pinfunction "GND_3") (pintype "bidirectional"))
      (node (ref "J1") (pin "17") (pinfunction "17_17") (pintype "bidirectional"))
      (node (ref "J1") (pin "8") (pinfunction "8_8") (pintype "bidirectional"))
      (node (ref "J1") (pin "MP1") (pinfunction "MP1_MP1") (pintype "bidirectional"))
      (node (ref "J1") (pin "MP2") (pinfunction "MP2_MP2") (pintype "bidirectional"))
      (node (ref "J2") (pin "A1") (pinfunction "A1_A1") (pintype "bidirectional"))
      (node (ref "J2") (pin "A12") (pinfunction "A12_A12") (pintype "bidirectional"))
      (node (ref "J2") (pin "B1") (pinfunction "B1_B1") (pintype "bidirectional"))
      (node (ref "J2") (pin "B12") (pinfunction "B12_B12") (pintype "bidirectional"))
      (node (ref "J2") (pin "MP1") (pinfunction "MP1_MP1") (pintype "bidirectional"))
      (node (ref "J2") (pin "MP2") (pinfunction "MP2_MP2") (pintype "bidirectional"))
      (node (ref "J2") (pin "MP3") (pinfunction "MP3_MP3") (pintype "bidirectional"))
      (node (ref "J2") (pin "MP4") (pinfunction "MP4_MP4") (pintype "bidirectional"))
      (node (ref "J3") (pin "1") (pinfunction "1_1") (pintype "power_in"))
      (node (ref "J4") (pin "G1") (pinfunction "GND_1_G1") (pintype "bidirectional"))
      (node (ref "J4") (pin "G2") (pinfunction "GND_2_G2") (pintype "bidirectional"))
      (node (ref "J4") (pin "G3") (pinfunction "GND_3_G3") (pintype "bidirectional"))
      (node (ref "J4") (pin "G4") (pinfunction "GND_4_G4") (pintype "bidirectional"))
      (node (ref "J4") (pin "P6") (pinfunction "VSS_P6") (pintype "bidirectional"))
      (node (ref "MCP73831") (pin "2") (pinfunction "VSS_2") (pintype "power_in"))
      (node (ref "R1_PWUSB") (pin "1") (pinfunction "1_1") (pintype "passive"))
      (node (ref "R2") (pin "1") (pinfunction "1_1") (pintype "passive"))
      (node (ref "R2-USB") (pin "2") (pinfunction "2_2") (pintype "passive"))
      (node (ref "R2-USB1") (pin "1") (pinfunction "1_1") (pintype "passive"))
      (node (ref "R2_BAT") (pin "1") (pinfunction "1_1") (pintype "passive"))
      (node (ref "R4") (pin "1") (pinfunction "1_1") (pintype "passive"))
      (node (ref "RESET_BUTTON") (pin "1") (pinfunction "1_1") (pintype "passive"))
      (node (ref "RESET_BUTTON") (pin "2") (pinfunction "2_2") (pintype "passive"))
      (node (ref "SENSOR2") (pin "1") (pinfunction "GND_1") (pintype "power_in"))
      (node (ref "SENSOR2") (pin "5") (pinfunction "SDO_5") (pintype "bidirectional"))
      (node (ref "SENSOR2") (pin "7") (pinfunction "GND_7") (pintype "power_in"))
      (node (ref "SJ1") (pin "1") (pinfunction "1_1") (pintype "passive"))
      (node (ref "TP4") (pin "TP") (pinfunction "TP_TP") (pintype "input"))
      (node (ref "TP5") (pin "TP") (pinfunction "TP_TP") (pintype "input"))
      (node (ref "U1") (pin "4") (pinfunction "GND_4") (pintype "power_in"))
      (node (ref "U1") (pin "9") (pinfunction "EXP_9") (pintype "passive"))
      (node (ref "U2") (pin "1") (pinfunction "GND_1") (pintype "power_in"))
      (node (ref "U2") (pin "28") (pinfunction "GND_28") (pintype "power_in"))
      (node (ref "U2") (pin "29_1") (pinfunction "GND_29_1") (pintype "power_in"))
      (node (ref "U2") (pin "29_2") (pinfunction "GND_29_2") (pintype "power_in"))
      (node (ref "U2") (pin "29_3") (pinfunction "GND_29_3") (pintype "power_in"))
      (node (ref "U2") (pin "29_4") (pinfunction "GND_29_4") (pintype "power_in"))
      (node (ref "U2") (pin "29_5") (pinfunction "GND_29_5") (pintype "power_in"))
      (node (ref "U2") (pin "29_6") (pinfunction "GND_29_6") (pintype "power_in"))
      (node (ref "U2") (pin "29_7") (pinfunction "GND_29_7") (pintype "power_in"))
      (node (ref "U2") (pin "29_8") (pinfunction "GND_29_8") (pintype "power_in"))
      (node (ref "U2") (pin "29_9") (pinfunction "GND_29_9") (pintype "power_in"))
      (node (ref "U3") (pin "13") (pinfunction "GND_13") (pintype "power_in"))
      (node (ref "U4") (pin "1") (pinfunction "CTG_1") (pintype "power_in"))
      (node (ref "U4") (pin "4") (pinfunction "GND_4") (pintype "power_in"))
      (node (ref "U4") (pin "6") (pinfunction "QSTRT_6") (pintype "input"))
      (node (ref "U4") (pin "9") (pinfunction "EP_9") (pintype "power_in"))
    )
    (net (code "14") (name "GPIO8") (class "Default")
      (node (ref "R1") (pin "1") (pinfunction "1_1") (pintype "passive"))
      (node (ref "U2") (pin "10") (pinfunction "IO8_10") (pintype "bidirectional"))
    )
    (net (code "15") (name "I2C_PW") (class "Default")
      (node (ref "C1") (pin "1") (pinfunction "1_1") (pintype "passive"))
      (node (ref "C2") (pin "1") (pinfunction "1_1") (pintype "passive"))
      (node (ref "R1_PINH") (pin "2") (pinfunction "2_2") (pintype "passive"))
      (node (ref "R2-PINH") (pin "2") (pinfunction "2_2") (pintype "passive"))
      (node (ref "SENSOR2") (pin "2") (pinfunction "CSB_2") (pintype "input"))
      (node (ref "SENSOR2") (pin "6") (pinfunction "VDDIO_6") (pintype "power_in"))
      (node (ref "SENSOR2") (pin "8") (pinfunction "VDD_8") (pintype "power_in"))
      (node (ref "U2") (pin "17") (pinfunction "IO19_17") (pintype "bidirectional"))
    )
    (net (code "16") (name "INT_RTC") (class "Default")
      (node (ref "R1_PINH1") (pin "1") (pinfunction "1_1") (pintype "passive"))
      (node (ref "TP15") (pin "TP") (pinfunction "TP_TP") (pintype "input"))
      (node (ref "U2") (pin "8") (pinfunction "IO0_8") (pintype "bidirectional"))
      (node (ref "U3") (pin "3") (pinfunction "SQW/~{INT}_3") (pintype "output"))
    )
    (net (code "17") (name "IO{slash}BOOT") (class "Default")
      (node (ref "BOOT_BUTTON") (pin "3") (pinfunction "3_3") (pintype "passive"))
      (node (ref "BOOT_BUTTON") (pin "4") (pinfunction "4_4") (pintype "passive"))
      (node (ref "C6") (pin "1") (pinfunction "1_1") (pintype "passive"))
      (node (ref "R_BOOT") (pin "1") (pinfunction "1_1") (pintype "passive"))
      (node (ref "U2") (pin "15") (pinfunction "IO9_15") (pintype "bidirectional"))
    )
    (net (code "18") (name "IO{slash}CHANGE") (class "Default")
      (node (ref "C10") (pin "1") (pinfunction "1_1") (pintype "passive"))
      (node (ref "CHANGE_BUTTON") (pin "3") (pinfunction "3_3") (pintype "passive"))
      (node (ref "CHANGE_BUTTON") (pin "4") (pinfunction "4_4") (pintype "passive"))
      (node (ref "R_CHANGE") (pin "1") (pinfunction "1_1") (pintype "passive"))
      (node (ref "U2") (pin "23") (pinfunction "IO15_23") (pintype "bidirectional"))
    )
    (net (code "19") (name "MISO") (class "Default")
      (node (ref "D12") (pin "2") (pinfunction "2_2") (pintype "passive"))
      (node (ref "J4") (pin "P7") (pinfunction "DAT0_P7") (pintype "bidirectional"))
      (node (ref "R8") (pin "1") (pinfunction "1_1") (pintype "passive"))
      (node (ref "TP6") (pin "TP") (pinfunction "TP_TP") (pintype "input"))
      (node (ref "U1") (pin "2") (pinfunction "DO(IO1)_2") (pintype "bidirectional"))
      (node (ref "U2") (pin "27") (pinfunction "IO2_27") (pintype "bidirectional"))
    )
    (net (code "20") (name "MOSI") (class "Default")
      (node (ref "D11") (pin "2") (pinfunction "2_2") (pintype "passive"))
      (node (ref "J1") (pin "14") (pinfunction "14_14") (pintype "bidirectional"))
      (node (ref "J4") (pin "P3") (pinfunction "CMD_P3") (pintype "bidirectional"))
      (node (ref "R7") (pin "1") (pinfunction "1_1") (pintype "passive"))
      (node (ref "TP7") (pin "TP") (pinfunction "TP_TP") (pintype "input"))
      (node (ref "U1") (pin "5") (pinfunction "DI(IO0)_5") (pintype "bidirectional"))
      (node (ref "U2") (pin "7") (pinfunction "IO7_7") (pintype "bidirectional"))
    )
    (net (code "21") (name "Net-(CHG_LED-PadC)") (class "Default")
      (node (ref "CHG_LED") (pin "C") (pinfunction "C_C") (pintype "passive"))
      (node (ref "R1_BAT") (pin "1") (pinfunction "1_1") (pintype "passive"))
    )
    (net (code "22") (name "Net-(D2-CATHODE)") (class "Default")
      (node (ref "C1_BAT1") (pin "1") (pinfunction "1_1") (pintype "passive"))
      (node (ref "D2") (pin "1") (pinfunction "CATHODE_1") (pintype "bidirectional"))
      (node (ref "IC1") (pin "1") (pinfunction "VIN_1") (pintype "bidirectional"))
      (node (ref "IC1") (pin "3") (pinfunction "CE_3") (pintype "bidirectional"))
      (node (ref "Q1") (pin "2") (pinfunction "S_2") (pintype "bidirectional"))
    )
    (net (code "23") (name "Net-(D3-A)") (class "Default")
      (node (ref "C4") (pin "1") (pinfunction "1_1") (pintype "passive"))
      (node (ref "D3") (pin "2") (pinfunction "A_2") (pintype "bidirectional"))
      (node (ref "D4") (pin "1") (pinfunction "K_1") (pintype "bidirectional"))
    )
    (net (code "24") (name "Net-(D7-CATHODE)") (class "Default")
      (node (ref "D7") (pin "1") (pinfunction "CATHODE_1") (pintype "bidirectional"))
      (node (ref "R_CAPACITOR") (pin "1") (pinfunction "1_1") (pintype "passive"))
    )
    (net (code "25") (name "Net-(EPD_C1-Pad2)") (class "Default")
      (node (ref "EPD_C1") (pin "2") (pinfunction "2_2") (pintype "passive"))
      (node (ref "J1") (pin "4") (pinfunction "4_4") (pintype "bidirectional"))
    )
    (net (code "26") (name "Net-(EPD_C2-Pad2)") (class "Default")
      (node (ref "EPD_C2") (pin "2") (pinfunction "2_2") (pintype "passive"))
      (node (ref "J1") (pin "5") (pinfunction "5_5") (pintype "bidirectional"))
    )
    (net (code "27") (name "Net-(EPD_C5-Pad2)") (class "Default")
      (node (ref "EPD_C5") (pin "2") (pinfunction "2_2") (pintype "passive"))
      (node (ref "J1") (pin "15") (pinfunction "15_15") (pintype "bidirectional"))
    )
    (net (code "28") (name "Net-(EPD_C6-Pad2)") (class "Default")
      (node (ref "EPD_C6") (pin "2") (pinfunction "2_2") (pintype "passive"))
      (node (ref "J1") (pin "18") (pinfunction "18_18") (pintype "bidirectional"))
    )
    (net (code "29") (name "Net-(EPD_C7-Pad2)") (class "Default")
      (node (ref "EPD_C7") (pin "2") (pinfunction "2_2") (pintype "passive"))
      (node (ref "J1") (pin "19") (pinfunction "19_19") (pintype "bidirectional"))
    )
    (net (code "30") (name "Net-(EPD_C8-Pad2)") (class "Default")
      (node (ref "EPD_C8") (pin "2") (pinfunction "2_2") (pintype "passive"))
      (node (ref "J1") (pin "20") (pinfunction "20_20") (pintype "bidirectional"))
    )
    (net (code "31") (name "Net-(EPD_C10-Pad2)") (class "Default")
      (node (ref "EPD_C10") (pin "2") (pinfunction "2_2") (pintype "passive"))
      (node (ref "J1") (pin "22") (pinfunction "22_22") (pintype "bidirectional"))
    )
    (net (code "32") (name "Net-(EPD_C12-Pad2)") (class "Default")
      (node (ref "EPD_C12") (pin "2") (pinfunction "2_2") (pintype "passive"))
      (node (ref "J1") (pin "24") (pinfunction "24_24") (pintype "bidirectional"))
    )
    (net (code "33") (name "Net-(IC5-CT)") (class "Default")
      (node (ref "C_DELAY") (pin "1") (pinfunction "1_1") (pintype "passive"))
      (node (ref "IC5") (pin "5") (pinfunction "CT_5") (pintype "bidirectional"))
    )
    (net (code "34") (name "Net-(J2-PadA5)") (class "Default")
      (node (ref "J2") (pin "A5") (pinfunction "A5_A5") (pintype "bidirectional"))
      (node (ref "R2-USB1") (pin "2") (pinfunction "2_2") (pintype "passive"))
    )
    (net (code "35") (name "Net-(J2-PadB5)") (class "Default")
      (node (ref "J2") (pin "B5") (pinfunction "B5_B5") (pintype "bidirectional"))
      (node (ref "R2-USB") (pin "1") (pinfunction "1_1") (pintype "passive"))
    )
    (net (code "36") (name "Net-(MCP73831-PROG)") (class "Default")
      (node (ref "MCP73831") (pin "5") (pinfunction "PROG_5") (pintype "input"))
      (node (ref "R2_BAT") (pin "2") (pinfunction "2_2") (pintype "passive"))
    )
    (net (code "37") (name "Net-(MCP73831-STAT)") (class "Default")
      (node (ref "MCP73831") (pin "1") (pinfunction "STAT_1") (pintype "output"))
      (node (ref "R1_BAT") (pin "2") (pinfunction "2_2") (pintype "passive"))
    )
    (net (code "38") (name "PREVGH") (class "Default")
      (node (ref "D5") (pin "1") (pinfunction "K_1") (pintype "bidirectional"))
      (node (ref "EPD_C9") (pin "2") (pinfunction "2_2") (pintype "passive"))
      (node (ref "J1") (pin "21") (pinfunction "21_21") (pintype "bidirectional"))
    )
    (net (code "39") (name "PREVGL") (class "Default")
      (node (ref "D4") (pin "2") (pinfunction "A_2") (pintype "bidirectional"))
      (node (ref "EPD_C11") (pin "2") (pinfunction "2_2") (pintype "passive"))
      (node (ref "J1") (pin "23") (pinfunction "23_23") (pintype "bidirectional"))
    )
    (net (code "40") (name "RESE") (class "Default")
      (node (ref "J1") (pin "3") (pinfunction "3_3") (pintype "bidirectional"))
      (node (ref "Q3") (pin "2") (pinfunction "S_2") (pintype "bidirectional"))
      (node (ref "R2") (pin "2") (pinfunction "2_2") (pintype "passive"))
      (node (ref "R3") (pin "2") (pinfunction "2_2") (pintype "passive"))
      (node (ref "SJ1") (pin "2") (pinfunction "2_2") (pintype "passive"))
    )
    (net (code "41") (name "RESE'") (class "Default")
      (node (ref "R3") (pin "1") (pinfunction "1_1") (pintype "passive"))
    )
    (net (code "42") (name "RESET") (class "Default")
      (node (ref "C5") (pin "1") (pinfunction "1_1") (pintype "passive"))
      (node (ref "IC5") (pin "1") (pinfunction "VOUT_1") (pintype "bidirectional"))
      (node (ref "RESET_BUTTON") (pin "3") (pinfunction "3_3") (pintype "passive"))
      (node (ref "RESET_BUTTON") (pin "4") (pinfunction "4_4") (pintype "passive"))
      (node (ref "R_RESET") (pin "1") (pinfunction "1_1") (pintype "passive"))
      (node (ref "U2") (pin "3") (pinfunction "EN_3") (pintype "input"))
    )
    (net (code "43") (name "RTC_RST") (class "Default")
      (node (ref "U2") (pin "16") (pinfunction "IO18_16") (pintype "bidirectional"))
      (node (ref "U3") (pin "4") (pinfunction "~{RST}_4") (pintype "input"))
    )
    (net (code "44") (name "RX") (class "Default")
      (node (ref "TP2") (pin "TP") (pinfunction "TP_TP") (pintype "input"))
      (node (ref "U2") (pin "24") (pinfunction "RXD0/GPIO17_24") (pintype "bidirectional"))
    )
    (net (code "45") (name "SCK") (class "Default")
      (node (ref "D10") (pin "2") (pinfunction "2_2") (pintype "passive"))
      (node (ref "J1") (pin "13") (pinfunction "13_13") (pintype "bidirectional"))
      (node (ref "J4") (pin "P5") (pinfunction "CLK_P5") (pintype "bidirectional"))
      (node (ref "R6") (pin "1") (pinfunction "1_1") (pintype "passive"))
      (node (ref "TP8") (pin "TP") (pinfunction "TP_TP") (pintype "input"))
      (node (ref "U1") (pin "6") (pinfunction "CLK_6") (pintype "input"))
      (node (ref "U2") (pin "6") (pinfunction "IO6_6") (pintype "bidirectional"))
    )
    (net (code "46") (name "SCL") (class "Default")
      (node (ref "J3") (pin "4") (pinfunction "4_4") (pintype "passive"))
      (node (ref "R2-PINH") (pin "1") (pinfunction "1_1") (pintype "passive"))
      (node (ref "SENSOR2") (pin "4") (pinfunction "SCK_4") (pintype "input"))
      (node (ref "U2") (pin "20") (pinfunction "IO22_20") (pintype "bidirectional"))
      (node (ref "U3") (pin "16") (pinfunction "SCL_16") (pintype "input"))
      (node (ref "U4") (pin "5") (pinfunction "~{ALERT}_5") (pintype "output"))
      (node (ref "U4") (pin "7") (pinfunction "SCL_7") (pintype "input"))
    )
    (net (code "47") (name "SDA") (class "Default")
      (node (ref "J3") (pin "3") (pinfunction "3_3") (pintype "passive"))
      (node (ref "R1_PINH") (pin "1") (pinfunction "1_1") (pintype "passive"))
      (node (ref "SENSOR2") (pin "3") (pinfunction "SDI_3") (pintype "bidirectional"))
      (node (ref "U2") (pin "19") (pinfunction "IO21_19") (pintype "bidirectional"))
      (node (ref "U3") (pin "15") (pinfunction "SDA_15") (pintype "bidirectional"))
      (node (ref "U4") (pin "8") (pinfunction "SDA_8") (pintype "bidirectional"))
    )
    (net (code "48") (name "SRC") (class "Default")
      (node (ref "C4") (pin "2") (pinfunction "2_2") (pintype "passive"))
      (node (ref "D5") (pin "2") (pinfunction "A_2") (pintype "bidirectional"))
      (node (ref "L1") (pin "1") (pinfunction "1_1") (pintype "passive"))
      (node (ref "Q3") (pin "3") (pinfunction "D_3") (pintype "bidirectional"))
    )
    (net (code "49") (name "SS_SD") (class "Default")
      (node (ref "D8") (pin "2") (pinfunction "2_2") (pintype "passive"))
      (node (ref "J4") (pin "P2") (pinfunction "CD/DAT3_P2") (pintype "bidirectional"))
      (node (ref "R10") (pin "1") (pinfunction "1_1") (pintype "passive"))
      (node (ref "U2") (pin "4") (pinfunction "IO4_4") (pintype "bidirectional"))
    )
    (net (code "50") (name "TX") (class "Default")
      (node (ref "TP1") (pin "TP") (pinfunction "TP_TP") (pintype "input"))
      (node (ref "U2") (pin "25") (pinfunction "TXD0/GPIO16_25") (pintype "bidirectional"))
    )
    (net (code "51") (name "USB_D+") (class "Default")
      (node (ref "D1") (pin "1") (pinfunction "I/O1_1_1") (pintype "bidirectional"))
      (node (ref "U2") (pin "14") (pinfunction "IO13_14") (pintype "bidirectional"))
    )
    (net (code "52") (name "USB_D-") (class "Default")
      (node (ref "D1") (pin "3") (pinfunction "I/O2_1_3") (pintype "bidirectional"))
      (node (ref "U2") (pin "13") (pinfunction "IO12_13") (pintype "bidirectional"))
    )
    (net (code "53") (name "VBAT") (class "Default")
      (node (ref "C2_BAT") (pin "1") (pinfunction "1_1") (pintype "passive"))
      (node (ref "MCP73831") (pin "3") (pinfunction "VBAT_3") (pintype "power_in"))
      (node (ref "Q1") (pin "3") (pinfunction "D_3") (pintype "bidirectional"))
      (node (ref "TP3") (pin "TP") (pinfunction "TP_TP") (pintype "input"))
      (node (ref "U4") (pin "2") (pinfunction "CELL_2") (pintype "power_in"))
      (node (ref "U4") (pin "3") (pinfunction "VDD_3") (pintype "power_in"))
    )
    (net (code "54") (name "VBUS") (class "Default")
      (node (ref "C1_BAT") (pin "1") (pinfunction "1_1") (pintype "passive"))
      (node (ref "C4_USB") (pin "1") (pinfunction "1_1") (pintype "passive"))
      (node (ref "C5_USB") (pin "1") (pinfunction "1_1") (pintype "passive"))
      (node (ref "CHG_LED") (pin "A") (pinfunction "A_A") (pintype "passive"))
      (node (ref "D1") (pin "5") (pinfunction "VBUS_5") (pintype "bidirectional"))
      (node (ref "D2") (pin "2") (pinfunction "ANODE_2") (pintype "bidirectional"))
      (node (ref "J2") (pin "B9") (pinfunction "B9_B9") (pintype "bidirectional"))
      (node (ref "MCP73831") (pin "4") (pinfunction "VIN_4") (pintype "power_in"))
      (node (ref "PFMF.050.1") (pin "2") (pinfunction "2_2") (pintype "passive"))
      (node (ref "Q1") (pin "1") (pinfunction "G_1") (pintype "bidirectional"))
      (node (ref "R1_PWUSB") (pin "2") (pinfunction "2_2") (pintype "passive"))
      (node (ref "TP14") (pin "TP") (pinfunction "TP_TP") (pintype "input"))
    )
    (net (code "55") (name "VRTC") (class "Default")
      (node (ref "C10_SUPERCAP") (pin "1") (pinfunction "1_1") (pintype "passive"))
      (node (ref "C8") (pin "1") (pinfunction "1_1") (pintype "passive"))
      (node (ref "R_CAPACITOR") (pin "2") (pinfunction "2_2") (pintype "passive"))
      (node (ref "U3") (pin "14") (pinfunction "VBAT_14") (pintype "power_in"))
    )
    (net (code "56") (name "VUSB") (class "Default")
      (node (ref "J2") (pin "A4") (pinfunction "A4_A4") (pintype "bidirectional"))
      (node (ref "J2") (pin "A9") (pinfunction "A9_A9") (pintype "bidirectional"))
      (node (ref "J2") (pin "B4") (pinfunction "B4_B4") (pintype "bidirectional"))
      (node (ref "PFMF.050.1") (pin "1") (pinfunction "1_1") (pintype "passive"))
    )
    (net (code "57") (name "unconnected-(IC1-NC-Pad4)") (class "Default")
      (node (ref "IC1") (pin "4") (pinfunction "NC_4") (pintype "no_connect"))
    )
    (net (code "58") (name "unconnected-(IC5-NC-Pad4)") (class "Default")
      (node (ref "IC5") (pin "4") (pinfunction "NC_4") (pintype "no_connect"))
    )
    (net (code "59") (name "unconnected-(J1-Pad1)") (class "Default")
      (node (ref "J1") (pin "1") (pinfunction "1_1") (pintype "bidirectional"))
    )
    (net (code "60") (name "unconnected-(J1-Pad6)") (class "Default")
      (node (ref "J1") (pin "6") (pinfunction "6_6") (pintype "bidirectional"))
    )
    (net (code "61") (name "unconnected-(J1-Pad7)") (class "Default")
      (node (ref "J1") (pin "7") (pinfunction "7_7") (pintype "bidirectional"))
    )
    (net (code "62") (name "unconnected-(J2-PadA8)") (class "Default")
      (node (ref "J2") (pin "A8") (pinfunction "A8_A8") (pintype "bidirectional"))
    )
    (net (code "63") (name "unconnected-(J2-PadB8)") (class "Default")
      (node (ref "J2") (pin "B8") (pinfunction "B8_B8") (pintype "bidirectional"))
    )
    (net (code "64") (name "unconnected-(J4-DAT1-PadP8)") (class "Default")
      (node (ref "J4") (pin "P8") (pinfunction "DAT1_P8") (pintype "bidirectional"))
    )
    (net (code "65") (name "unconnected-(J4-DAT2-PadP1)") (class "Default")
      (node (ref "J4") (pin "P1") (pinfunction "DAT2_P1") (pintype "bidirectional"))
    )
    (net (code "66") (name "unconnected-(J4-DETECTION_1-PadS1)") (class "Default")
      (node (ref "J4") (pin "S1") (pinfunction "DETECTION_1_S1") (pintype "bidirectional"))
    )
    (net (code "67") (name "unconnected-(J4-DETECTION_2-PadS2)") (class "Default")
      (node (ref "J4") (pin "S2") (pinfunction "DETECTION_2_S2") (pintype "bidirectional"))
    )
    (net (code "68") (name "unconnected-(U2-NC-Pad22)") (class "Default")
      (node (ref "U2") (pin "22") (pinfunction "NC_22") (pintype "no_connect"))
    )
  )
)
